# beacon.net
KiCad netlist of a schematic drawn in EAGLE
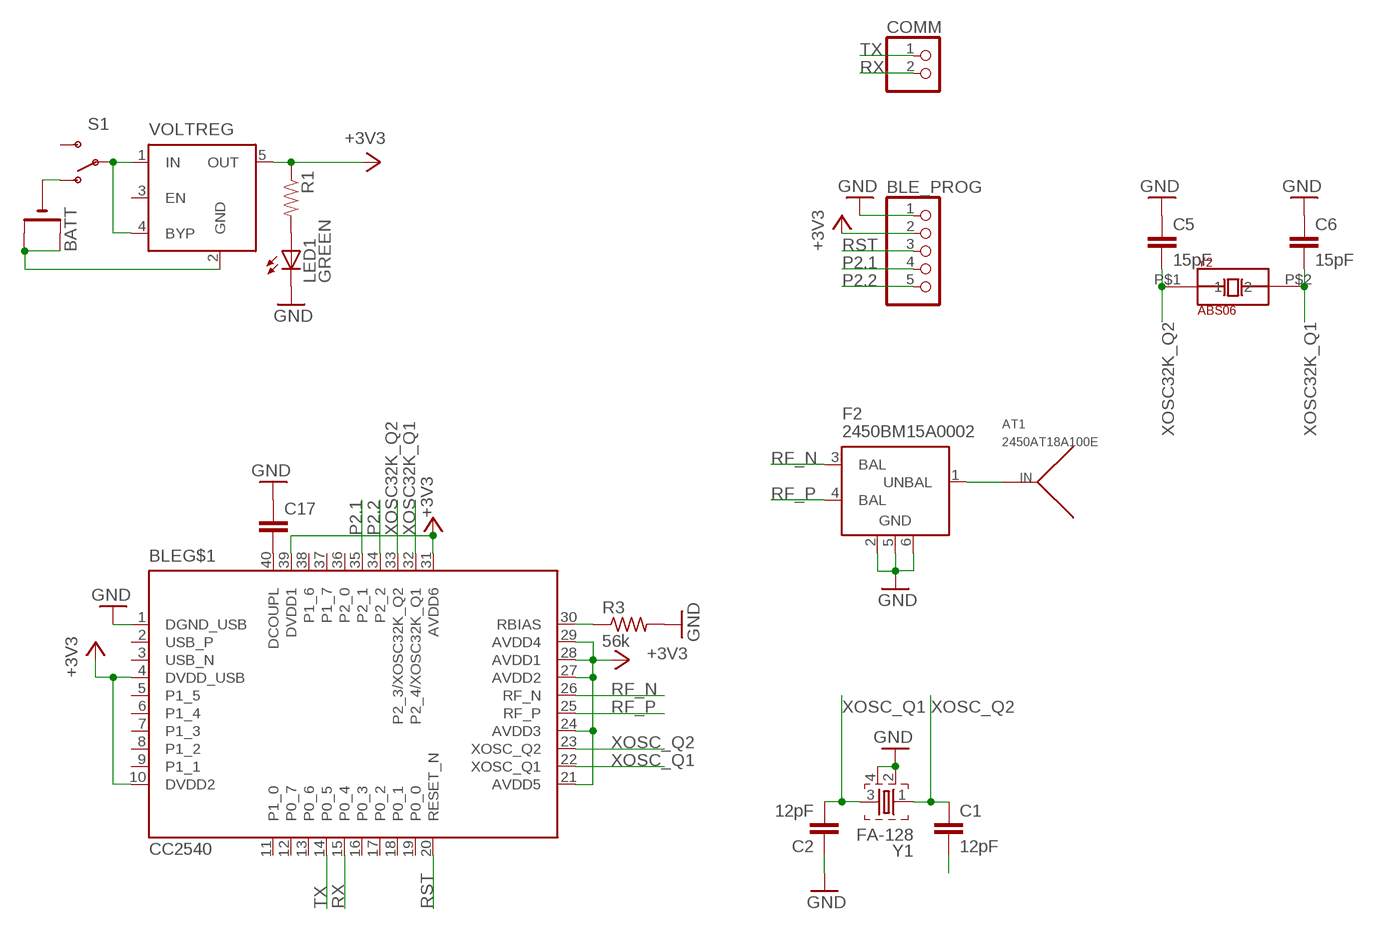
[diagram p0: schematic, sheet 1]

(export (version "E")
  (design (tool "Eeschema 10.0.6"))
  (components
    (comp (ref "AT1")
      (value "2450AT18A100E")
      (footprint "eagle-import:2450AT18A100E")
      (libsource (lib "eagle-import") (part "2450AT18A100E"))
    )
    (comp (ref "BATT")
      (value "CR2032SMT")
      (footprint "eagle-import:CR2032-SMD")
      (libsource (lib "eagle-import") (part "CR2032SMT"))
    )
    (comp (ref "BLE")
      (value "CC2540")
      (footprint "eagle-import:QFN40-6X6")
      (libsource (lib "eagle-import") (part "CC2540"))
    )
    (comp (ref "BLE_PROG")
      (value "PINHD-1X5")
      (footprint "eagle-import:1X05")
      (libsource (lib "eagle-import") (part "PINHD-1X5"))
    )
    (comp (ref "C1")
      (value "12pF")
      (footprint "eagle-import:C0402")
      (libsource (lib "eagle-import") (part "C-EUC0402"))
    )
    (comp (ref "C2")
      (value "12pF")
      (footprint "eagle-import:C0402")
      (libsource (lib "eagle-import") (part "C-EUC0402"))
    )
    (comp (ref "C5")
      (value "15pF")
      (footprint "eagle-import:C0402")
      (libsource (lib "eagle-import") (part "C-EUC0402"))
    )
    (comp (ref "C6")
      (value "15pF")
      (footprint "eagle-import:C0402")
      (libsource (lib "eagle-import") (part "C-EUC0402"))
    )
    (comp (ref "C17")
      (value "C-EUC0402")
      (footprint "eagle-import:C0402")
      (libsource (lib "eagle-import") (part "C-EUC0402"))
    )
    (comp (ref "COMM")
      (value "PINHD-1X2")
      (footprint "eagle-import:1X02")
      (libsource (lib "eagle-import") (part "PINHD-1X2"))
    )
    (comp (ref "F2")
      (value "2450BM15A0002")
      (footprint "eagle-import:2450BM15A0002")
      (libsource (lib "eagle-import") (part "2450BM15A0002"))
    )
    (comp (ref "LED1")
      (value "GREEN")
      (footprint "eagle-import:LED-0603")
      (libsource (lib "eagle-import") (part "LED-GREEN0603"))
    )
    (comp (ref "R1")
      (value "RESISTOR0402-RES")
      (footprint "eagle-import:0402-RES")
      (libsource (lib "eagle-import") (part "RESISTOR0402-RES"))
    )
    (comp (ref "R3")
      (value "56k")
      (footprint "eagle-import:R0402")
      (libsource (lib "eagle-import") (part "R-US_R0402"))
    )
    (comp (ref "S1")
      (value "SWITCH-SPDT-SMD-A")
      (footprint "eagle-import:SWITCH-SPST-SMD-A")
      (libsource (lib "eagle-import") (part "SWITCH-SPDT-SMD-A"))
    )
    (comp (ref "VOLTREG")
      (value "MIC5219XX")
      (footprint "eagle-import:SOT23-5")
      (libsource (lib "eagle-import") (part "MIC5219XX"))
    )
    (comp (ref "Y1")
      (value "FA-128")
      (footprint "eagle-import:FA-128")
      (libsource (lib "eagle-import") (part "FA-128"))
    )
    (comp (ref "Y2")
      (value "ABS06")
      (footprint "eagle-import:SMD")
      (libsource (lib "eagle-import") (part "ABS06"))
    )
  )
  (nets
    (net (code "1") (name "+3V3") (class "Default")
      (node (ref "BLE") (pin "10") (pinfunction "DVDD2_10") (pintype "power_in"))
      (node (ref "BLE") (pin "21") (pinfunction "AVDD5_21") (pintype "power_in"))
      (node (ref "BLE") (pin "24") (pinfunction "AVDD3_24") (pintype "power_in"))
      (node (ref "BLE") (pin "27") (pinfunction "AVDD2_27") (pintype "power_in"))
      (node (ref "BLE") (pin "28") (pinfunction "AVDD1_28") (pintype "power_in"))
      (node (ref "BLE") (pin "29") (pinfunction "AVDD4_29") (pintype "power_in"))
      (node (ref "BLE") (pin "31") (pinfunction "AVDD6_31") (pintype "power_in"))
      (node (ref "BLE") (pin "39") (pinfunction "DVDD1_39") (pintype "power_in"))
      (node (ref "BLE") (pin "4") (pinfunction "DVDD_USB_4") (pintype "power_in"))
      (node (ref "BLE_PROG") (pin "2") (pinfunction "2_2") (pintype "passive"))
      (node (ref "R1") (pin "1") (pinfunction "1_1") (pintype "passive"))
      (node (ref "VOLTREG") (pin "5") (pinfunction "OUT_5") (pintype "output"))
    )
    (net (code "2") (name "/P2.1") (class "Default")
      (node (ref "BLE") (pin "35") (pinfunction "P2_1_35") (pintype "bidirectional"))
      (node (ref "BLE_PROG") (pin "4") (pinfunction "4_4") (pintype "passive"))
    )
    (net (code "3") (name "/P2.2") (class "Default")
      (node (ref "BLE") (pin "34") (pinfunction "P2_2_34") (pintype "bidirectional"))
      (node (ref "BLE_PROG") (pin "5") (pinfunction "5_5") (pintype "passive"))
    )
    (net (code "4") (name "/RF_N") (class "Default")
      (node (ref "BLE") (pin "26") (pinfunction "RF_N_26") (pintype "input"))
      (node (ref "F2") (pin "3") (pinfunction "BAL_3") (pintype "passive"))
    )
    (net (code "5") (name "/RF_P") (class "Default")
      (node (ref "BLE") (pin "25") (pinfunction "RF_P_25") (pintype "input"))
      (node (ref "F2") (pin "4") (pinfunction "BAL_4") (pintype "passive"))
    )
    (net (code "6") (name "/RST") (class "Default")
      (node (ref "BLE") (pin "20") (pinfunction "RESET_N_20") (pintype "input"))
      (node (ref "BLE_PROG") (pin "3") (pinfunction "3_3") (pintype "passive"))
    )
    (net (code "7") (name "/RX") (class "Default")
      (node (ref "BLE") (pin "15") (pinfunction "P0_4_15") (pintype "bidirectional"))
      (node (ref "COMM") (pin "2") (pinfunction "2_2") (pintype "passive"))
    )
    (net (code "8") (name "/TX") (class "Default")
      (node (ref "BLE") (pin "14") (pinfunction "P0_5_14") (pintype "bidirectional"))
      (node (ref "COMM") (pin "1") (pinfunction "1_1") (pintype "passive"))
    )
    (net (code "9") (name "/XOSC32K_Q1") (class "Default")
      (node (ref "BLE") (pin "32") (pinfunction "P2_4/XOSC32K_Q1_32") (pintype "bidirectional"))
      (node (ref "C6") (pin "2") (pinfunction "2_2") (pintype "passive"))
      (node (ref "Y2") (pin "P$2") (pinfunction "2_P$2") (pintype "bidirectional"))
    )
    (net (code "10") (name "/XOSC32K_Q2") (class "Default")
      (node (ref "BLE") (pin "33") (pinfunction "P2_3/XOSC32K_Q2_33") (pintype "bidirectional"))
      (node (ref "C5") (pin "2") (pinfunction "2_2") (pintype "passive"))
      (node (ref "Y2") (pin "P$1") (pinfunction "1_P$1") (pintype "bidirectional"))
    )
    (net (code "11") (name "/XOSC_Q1") (class "Default")
      (node (ref "BLE") (pin "22") (pinfunction "XOSC_Q1_22") (pintype "bidirectional"))
      (node (ref "C2") (pin "2") (pinfunction "2_2") (pintype "passive"))
      (node (ref "Y1") (pin "3") (pinfunction "3_3") (pintype "passive"))
    )
    (net (code "12") (name "/XOSC_Q2") (class "Default")
      (node (ref "BLE") (pin "23") (pinfunction "XOSC_Q2_23") (pintype "bidirectional"))
      (node (ref "C1") (pin "1") (pinfunction "1_1") (pintype "passive"))
      (node (ref "Y1") (pin "1") (pinfunction "1_1") (pintype "passive"))
    )
    (net (code "13") (name "GND") (class "Default")
      (node (ref "BLE") (pin "1") (pinfunction "DGND_USB_1") (pintype "power_in"))
      (node (ref "BLE_PROG") (pin "1") (pinfunction "1_1") (pintype "passive"))
      (node (ref "C17") (pin "1") (pinfunction "1_1") (pintype "passive"))
      (node (ref "C2") (pin "1") (pinfunction "1_1") (pintype "passive"))
      (node (ref "C5") (pin "1") (pinfunction "1_1") (pintype "passive"))
      (node (ref "C6") (pin "1") (pinfunction "1_1") (pintype "passive"))
      (node (ref "F2") (pin "2") (pinfunction "GND_2") (pintype "passive"))
      (node (ref "F2") (pin "5") (pinfunction "GND_5") (pintype "passive"))
      (node (ref "F2") (pin "6") (pinfunction "GND_6") (pintype "passive"))
      (node (ref "LED1") (pin "C") (pinfunction "C_C") (pintype "passive"))
      (node (ref "R3") (pin "2") (pinfunction "2_2") (pintype "passive"))
      (node (ref "Y1") (pin "2") (pinfunction "2_2") (pintype "passive"))
      (node (ref "Y1") (pin "4") (pinfunction "4_4") (pintype "passive"))
    )
    (net (code "14") (name "Net-(AT1-IN)") (class "Default")
      (node (ref "AT1") (pin "P$1") (pinfunction "IN_P$1") (pintype "input"))
      (node (ref "F2") (pin "1") (pinfunction "UNBAL_1") (pintype "passive"))
    )
    (net (code "15") (name "Net-(BATT-+)") (class "Default")
      (node (ref "BATT") (pin "+$1") (pinfunction "+_+$1") (pintype "passive"))
      (node (ref "BATT") (pin "+$2") (pinfunction "+1_+$2") (pintype "passive"))
      (node (ref "VOLTREG") (pin "2") (pinfunction "GND_2") (pintype "power_in"))
    )
    (net (code "16") (name "Net-(BLEB-DCOUPL)") (class "Default")
      (node (ref "BLE") (pin "40") (pinfunction "DCOUPL_40") (pintype "power_in"))
      (node (ref "C17") (pin "2") (pinfunction "2_2") (pintype "passive"))
    )
    (net (code "17") (name "Net-(BLEB-RBIAS)") (class "Default")
      (node (ref "BLE") (pin "30") (pinfunction "RBIAS_30") (pintype "bidirectional"))
      (node (ref "R3") (pin "1") (pinfunction "1_1") (pintype "passive"))
    )
    (net (code "18") (name "Net-(LED1-PadA)") (class "Default")
      (node (ref "LED1") (pin "A") (pinfunction "A_A") (pintype "passive"))
      (node (ref "R1") (pin "2") (pinfunction "2_2") (pintype "passive"))
    )
    (net (code "19") (name "Net-(S1-O)") (class "Default")
      (node (ref "BATT") (pin "-") (pinfunction "-_-") (pintype "passive"))
      (node (ref "S1") (pin "1") (pinfunction "O_1") (pintype "passive"))
    )
    (net (code "20") (name "Net-(S1-P)") (class "Default")
      (node (ref "S1") (pin "2") (pinfunction "P_2") (pintype "passive"))
      (node (ref "VOLTREG") (pin "1") (pinfunction "IN_1") (pintype "input"))
      (node (ref "VOLTREG") (pin "4") (pinfunction "BYP_4") (pintype "passive"))
    )
    (net (code "21") (name "unconnected-(BLEB-P0_0-Pad19)") (class "Default")
      (node (ref "BLE") (pin "19") (pinfunction "P0_0_19") (pintype "bidirectional"))
    )
    (net (code "22") (name "unconnected-(BLEB-P0_1-Pad18)") (class "Default")
      (node (ref "BLE") (pin "18") (pinfunction "P0_1_18") (pintype "bidirectional"))
    )
    (net (code "23") (name "unconnected-(BLEB-P0_2-Pad17)") (class "Default")
      (node (ref "BLE") (pin "17") (pinfunction "P0_2_17") (pintype "bidirectional"))
    )
    (net (code "24") (name "unconnected-(BLEB-P0_3-Pad16)") (class "Default")
      (node (ref "BLE") (pin "16") (pinfunction "P0_3_16") (pintype "bidirectional"))
    )
    (net (code "25") (name "unconnected-(BLEB-P0_6-Pad13)") (class "Default")
      (node (ref "BLE") (pin "13") (pinfunction "P0_6_13") (pintype "bidirectional"))
    )
    (net (code "26") (name "unconnected-(BLEB-P0_7-Pad12)") (class "Default")
      (node (ref "BLE") (pin "12") (pinfunction "P0_7_12") (pintype "bidirectional"))
    )
    (net (code "27") (name "unconnected-(BLEB-P1_0-Pad11)") (class "Default")
      (node (ref "BLE") (pin "11") (pinfunction "P1_0_11") (pintype "bidirectional"))
    )
    (net (code "28") (name "unconnected-(BLEB-P1_1-Pad9)") (class "Default")
      (node (ref "BLE") (pin "9") (pinfunction "P1_1_9") (pintype "bidirectional"))
    )
    (net (code "29") (name "unconnected-(BLEB-P1_2-Pad8)") (class "Default")
      (node (ref "BLE") (pin "8") (pinfunction "P1_2_8") (pintype "bidirectional"))
    )
    (net (code "30") (name "unconnected-(BLEB-P1_3-Pad7)") (class "Default")
      (node (ref "BLE") (pin "7") (pinfunction "P1_3_7") (pintype "bidirectional"))
    )
    (net (code "31") (name "unconnected-(BLEB-P1_4-Pad6)") (class "Default")
      (node (ref "BLE") (pin "6") (pinfunction "P1_4_6") (pintype "bidirectional"))
    )
    (net (code "32") (name "unconnected-(BLEB-P1_5-Pad5)") (class "Default")
      (node (ref "BLE") (pin "5") (pinfunction "P1_5_5") (pintype "bidirectional"))
    )
    (net (code "33") (name "unconnected-(BLEB-P1_6-Pad38)") (class "Default")
      (node (ref "BLE") (pin "38") (pinfunction "P1_6_38") (pintype "bidirectional"))
    )
    (net (code "34") (name "unconnected-(BLEB-P1_7-Pad37)") (class "Default")
      (node (ref "BLE") (pin "37") (pinfunction "P1_7_37") (pintype "bidirectional"))
    )
    (net (code "35") (name "unconnected-(BLEB-P2_0-Pad36)") (class "Default")
      (node (ref "BLE") (pin "36") (pinfunction "P2_0_36") (pintype "bidirectional"))
    )
    (net (code "36") (name "unconnected-(BLEB-USB_N-Pad3)") (class "Default")
      (node (ref "BLE") (pin "3") (pinfunction "USB_N_3") (pintype "bidirectional"))
    )
    (net (code "37") (name "unconnected-(BLEB-USB_P-Pad2)") (class "Default")
      (node (ref "BLE") (pin "2") (pinfunction "USB_P_2") (pintype "bidirectional"))
    )
    (net (code "38") (name "unconnected-(C1-Pad2)") (class "Default")
      (node (ref "C1") (pin "2") (pinfunction "2_2") (pintype "passive"))
    )
    (net (code "39") (name "unconnected-(S1-S-Pad3)") (class "Default")
      (node (ref "S1") (pin "3") (pinfunction "S_3") (pintype "passive"))
    )
    (net (code "40") (name "unconnected-(VOLTREG-EN-Pad3)") (class "Default")
      (node (ref "VOLTREG") (pin "3") (pinfunction "EN_3") (pintype "input"))
    )
  )
)
